# MCU_and_Power_Man.net
KiCad netlist of a schematic drawn in Altium Designer
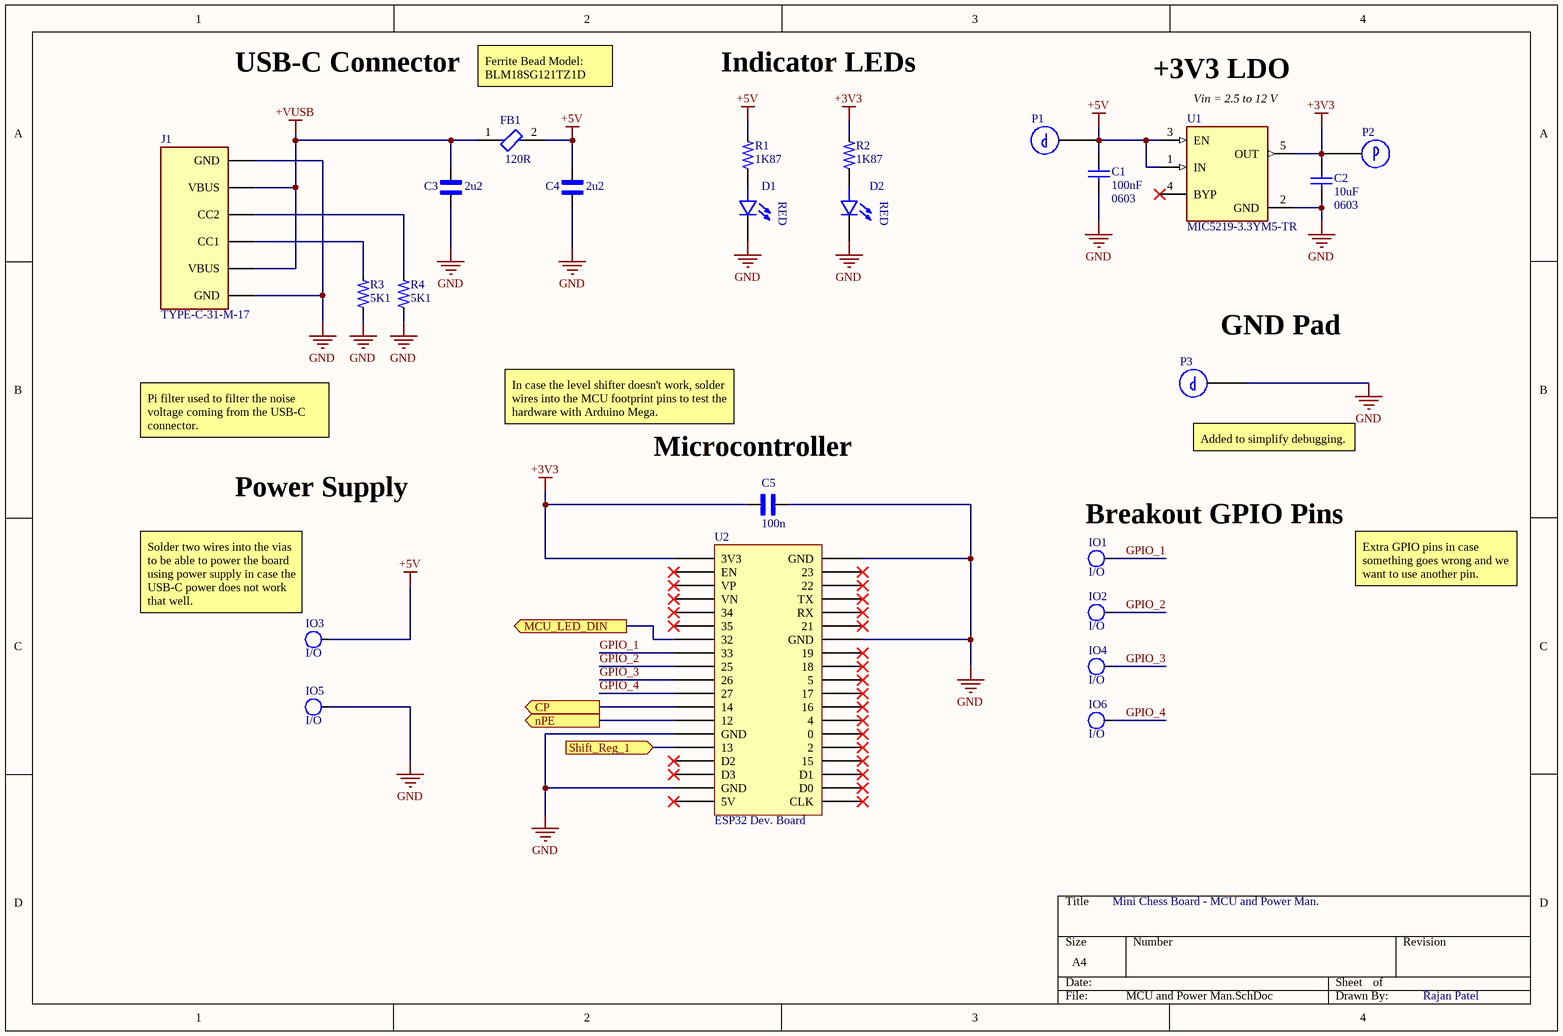
[diagram p0: MCU and Power Man.SchDoc]

(export (version "E")
  (design (tool "Eeschema 10.0.6"))
  (components
    (comp (ref "C1")
      (value "100nF")
      (footprint "CAP 0805")
      (description "Capacitor")
      (fields (field (name "ALTIUM_VALUE") "0603") (field (name "PUBLISHER") "Altium Limited"))
      (libsource (lib "Miscellaneous Devices") (part "Cap"))
    )
    (comp (ref "C2")
      (value "10uF")
      (footprint "CAP 0805")
      (description "Capacitor")
      (fields (field (name "ALTIUM_VALUE") "0603") (field (name "PUBLISHER") "Altium Limited"))
      (libsource (lib "Miscellaneous Devices") (part "Cap"))
    )
    (comp (ref "C3")
      (value "2u2")
      (footprint "CAP 0805")
      (libsource (lib "ChessBoardSchLib") (part "CAP 0805"))
    )
    (comp (ref "C4")
      (value "2u2")
      (footprint "CAP 0805")
      (libsource (lib "ChessBoardSchLib") (part "CAP 0805"))
    )
    (comp (ref "C5")
      (value "100n")
      (footprint "CAP 0805")
      (libsource (lib "ChessBoardSchLib") (part "CAP 0805"))
    )
    (comp (ref "D1")
      (value "LED 0805")
      (footprint "LED_0805")
      (description "Red LED Indication - Discrete 1.7V 0805 (2012 Metric)")
      (fields (field (name "MP") "7012X1"))
      (libsource (lib "ChessBoardSchLib") (part "LED 0805"))
    )
    (comp (ref "D2")
      (value "LED 0805")
      (footprint "LED_0805")
      (description "Red LED Indication - Discrete 1.7V 0805 (2012 Metric)")
      (fields (field (name "MP") "7012X1"))
      (libsource (lib "ChessBoardSchLib") (part "LED 0805"))
    )
    (comp (ref "FB1")
      (value "120R")
      (footprint "FP-BLM21-0_2-t0_85-e0_5-IPC_A")
      (description "FERRITE BEAD 120 OHM 0603 1LN")
      (fields (field (name "TOLERANCE") "25%"))
      (libsource (lib "Altium Content Vault") (part "5f30dd21d616792df468990f7003faa"))
    )
    (comp (ref "IO1") (value "I/O") (footprint "I/O") (libsource (lib "MiniChessBoardSchLib") (part "I/O")))
    (comp (ref "IO2") (value "I/O") (footprint "I/O") (libsource (lib "MiniChessBoardSchLib") (part "I/O")))
    (comp (ref "IO3") (value "I/O") (footprint "I/O") (libsource (lib "MiniChessBoardSchLib") (part "I/O")))
    (comp (ref "IO4") (value "I/O") (footprint "I/O") (libsource (lib "MiniChessBoardSchLib") (part "I/O")))
    (comp (ref "IO5") (value "I/O") (footprint "I/O") (libsource (lib "MiniChessBoardSchLib") (part "I/O")))
    (comp (ref "IO6") (value "I/O") (footprint "I/O") (libsource (lib "MiniChessBoardSchLib") (part "I/O")))
    (comp (ref "J1")
      (value "TYPE-C-31-M-17")
      (footprint "TYPEC31M17")
      (description "TYPE-C-31-M-17 HROPARTS")
      (fields (field (name "MF") "HRO Electronics Co., Ltd."))
      (libsource (lib "ChessBoardSchLib") (part "TYPE-C-31-M-17"))
    )
    (comp (ref "P1")
      (value "Probe_5019")
      (footprint "Testpoint")
      (description "Phosphor Bronze Contact Miniature Silver Plated Surface Mount Test Points")
      (fields
        (field (name "MANUFACTURER") "Keystone Electronics")
        (field (name "MANUFACTURER PART NUMBER") "5019")
      )
      (libsource (lib "MiniChessBoardSchLib") (part "Probe_5019"))
    )
    (comp (ref "P2")
      (value "Probe_5019")
      (footprint "Testpoint")
      (description "Phosphor Bronze Contact Miniature Silver Plated Surface Mount Test Points")
      (fields
        (field (name "MANUFACTURER") "Keystone Electronics")
        (field (name "MANUFACTURER PART NUMBER") "5019")
      )
      (libsource (lib "MiniChessBoardSchLib") (part "Probe_5019"))
    )
    (comp (ref "P3")
      (value "Probe_5019")
      (footprint "Testpoint")
      (description "Phosphor Bronze Contact Miniature Silver Plated Surface Mount Test Points")
      (fields
        (field (name "MANUFACTURER") "Keystone Electronics")
        (field (name "MANUFACTURER PART NUMBER") "5019")
      )
      (libsource (lib "MiniChessBoardSchLib") (part "Probe_5019"))
    )
    (comp (ref "R1")
      (value "1K87")
      (footprint "res 0805")
      (fields
        (field (name "MP") "2-2176053-2")
        (field (name "MF") "TE Connectivity")
        (field (name "TOLERANCE") "1%")
      )
      (libsource (lib "ChessBoardSchLib") (part "Resistor 0805"))
    )
    (comp (ref "R2")
      (value "1K87")
      (footprint "res 0805")
      (fields
        (field (name "MP") "2-2176053-2")
        (field (name "MF") "TE Connectivity")
        (field (name "TOLERANCE") "1%")
      )
      (libsource (lib "ChessBoardSchLib") (part "Resistor 0805"))
    )
    (comp (ref "R3")
      (value "5K1")
      (footprint "res 0805")
      (fields
        (field (name "MP") "2-2176053-2")
        (field (name "MF") "TE Connectivity")
        (field (name "TOLERANCE") "1%")
      )
      (libsource (lib "ChessBoardSchLib") (part "Resistor 0805"))
    )
    (comp (ref "R4")
      (value "5K1")
      (footprint "res 0805")
      (fields
        (field (name "MP") "2-2176053-2")
        (field (name "MF") "TE Connectivity")
        (field (name "TOLERANCE") "1%")
      )
      (libsource (lib "ChessBoardSchLib") (part "Resistor 0805"))
    )
    (comp (ref "U1")
      (value "MIC5219-3.3YM5-TR")
      (footprint "FP-SOT23-5LD-PL-1-IPC_C")
      (description "IC REG LINEAR 3.3V 500MA SOT23-5")
      (libsource (lib "Altium Content Vault") (part "16b36b16d6b7b40c29ab14718bc3058"))
    )
    (comp (ref "U2")
      (value "ESP32 Dev. Board")
      (footprint "ESPRESSIF_ESP32-DEVKITC-32UE")
      (fields
        (field (name "MANUFACTURER") "Espressif Systems")
        (field (name "MANUFACTURER PART NUMBER") "ESP32-DEVKITC-32UE")
      )
      (libsource (lib "ChessBoardSchLib") (part "ESP32 Dev. Board"))
    )
  )
  (nets
    (net (code "1") (name "+3V3") (class "Default")
      (node (ref "C2") (pin "2") (pinfunction "2_2") (pintype "passive"))
      (node (ref "C5") (pin "2") (pinfunction "2_2") (pintype "passive"))
      (node (ref "P2") (pin "1") (pinfunction "1_1") (pintype "passive"))
      (node (ref "R2") (pin "2") (pinfunction "2_2") (pintype "passive"))
      (node (ref "U1") (pin "5") (pinfunction "OUT_5") (pintype "output"))
      (node (ref "U2") (pin "1") (pinfunction "3V3_1") (pintype "passive"))
    )
    (net (code "2") (name "+5V") (class "Default")
      (node (ref "C1") (pin "2") (pinfunction "2_2") (pintype "passive"))
      (node (ref "C4") (pin "2") (pinfunction "2_2") (pintype "passive"))
      (node (ref "FB1") (pin "2") (pinfunction "2_2") (pintype "passive"))
      (node (ref "IO3") (pin "1") (pinfunction "1_1") (pintype "passive"))
      (node (ref "P1") (pin "1") (pinfunction "1_1") (pintype "passive"))
      (node (ref "R1") (pin "2") (pinfunction "2_2") (pintype "passive"))
      (node (ref "U1") (pin "1") (pinfunction "IN_1") (pintype "input"))
      (node (ref "U1") (pin "3") (pinfunction "EN_3") (pintype "input"))
    )
    (net (code "3") (name "+VUSB") (class "Default")
      (node (ref "C3") (pin "2") (pinfunction "2_2") (pintype "passive"))
      (node (ref "FB1") (pin "1") (pinfunction "1_1") (pintype "passive"))
      (node (ref "J1") (pin "2") (pinfunction "VBUS_2") (pintype "passive"))
      (node (ref "J1") (pin "5") (pinfunction "VBUS_5") (pintype "passive"))
    )
    (net (code "4") (name "/CP") (class "Default")
      (node (ref "U2") (pin "12") (pinfunction "14_12") (pintype "passive"))
    )
    (net (code "5") (name "/GPIO_1") (class "Default")
      (node (ref "IO1") (pin "1") (pinfunction "1_1") (pintype "passive"))
      (node (ref "U2") (pin "8") (pinfunction "33_8") (pintype "passive"))
    )
    (net (code "6") (name "/GPIO_2") (class "Default")
      (node (ref "IO2") (pin "1") (pinfunction "1_1") (pintype "passive"))
      (node (ref "U2") (pin "9") (pinfunction "25_9") (pintype "passive"))
    )
    (net (code "7") (name "/GPIO_3") (class "Default")
      (node (ref "IO4") (pin "1") (pinfunction "1_1") (pintype "passive"))
      (node (ref "U2") (pin "10") (pinfunction "26_10") (pintype "passive"))
    )
    (net (code "8") (name "/GPIO_4") (class "Default")
      (node (ref "IO6") (pin "1") (pinfunction "1_1") (pintype "passive"))
      (node (ref "U2") (pin "11") (pinfunction "27_11") (pintype "passive"))
    )
    (net (code "9") (name "/MCU_LED_DIN") (class "Default")
      (node (ref "U2") (pin "7") (pinfunction "32_7") (pintype "passive"))
    )
    (net (code "10") (name "/Shift_Reg_1") (class "Default")
      (node (ref "U2") (pin "15") (pinfunction "13_15") (pintype "passive"))
    )
    (net (code "11") (name "/nPE") (class "Default")
      (node (ref "U2") (pin "13") (pinfunction "12_13") (pintype "passive"))
    )
    (net (code "12") (name "GND") (class "Default")
      (node (ref "C1") (pin "1") (pinfunction "1_1") (pintype "passive"))
      (node (ref "C2") (pin "1") (pinfunction "1_1") (pintype "passive"))
      (node (ref "C3") (pin "1") (pinfunction "1_1") (pintype "passive"))
      (node (ref "C4") (pin "1") (pinfunction "1_1") (pintype "passive"))
      (node (ref "C5") (pin "1") (pinfunction "1_1") (pintype "passive"))
      (node (ref "D1") (pin "1") (pinfunction "C_1") (pintype "passive"))
      (node (ref "D2") (pin "1") (pinfunction "C_1") (pintype "passive"))
      (node (ref "IO5") (pin "1") (pinfunction "1_1") (pintype "passive"))
      (node (ref "J1") (pin "1") (pinfunction "GND_1") (pintype "passive"))
      (node (ref "J1") (pin "6") (pinfunction "GND_6") (pintype "passive"))
      (node (ref "P3") (pin "1") (pinfunction "1_1") (pintype "passive"))
      (node (ref "R3") (pin "1") (pinfunction "1_1") (pintype "passive"))
      (node (ref "R4") (pin "1") (pinfunction "1_1") (pintype "passive"))
      (node (ref "U1") (pin "2") (pinfunction "GND_2") (pintype "power_in"))
      (node (ref "U2") (pin "14") (pinfunction "GND_14") (pintype "passive"))
      (node (ref "U2") (pin "18") (pinfunction "GND_18") (pintype "passive"))
      (node (ref "U2") (pin "32") (pinfunction "GND_32") (pintype "passive"))
      (node (ref "U2") (pin "38") (pinfunction "GND_38") (pintype "passive"))
    )
    (net (code "13") (name "Net-(D1-A)") (class "Default")
      (node (ref "D1") (pin "2") (pinfunction "A_2") (pintype "passive"))
      (node (ref "R1") (pin "1") (pinfunction "1_1") (pintype "passive"))
    )
    (net (code "14") (name "Net-(D2-A)") (class "Default")
      (node (ref "D2") (pin "2") (pinfunction "A_2") (pintype "passive"))
      (node (ref "R2") (pin "1") (pinfunction "1_1") (pintype "passive"))
    )
    (net (code "15") (name "Net-(J1-CC1)") (class "Default")
      (node (ref "J1") (pin "3") (pinfunction "CC1_3") (pintype "passive"))
      (node (ref "R3") (pin "2") (pinfunction "2_2") (pintype "passive"))
    )
    (net (code "16") (name "Net-(J1-CC2)") (class "Default")
      (node (ref "J1") (pin "4") (pinfunction "CC2_4") (pintype "passive"))
      (node (ref "R4") (pin "2") (pinfunction "2_2") (pintype "passive"))
    )
    (net (code "17") (name "unconnected-(U1-BYP-Pad4)") (class "Default")
      (node (ref "U1") (pin "4") (pinfunction "BYP_4") (pintype "passive+no_connect"))
    )
    (net (code "18") (name "unconnected-(U2-0-Pad25)") (class "Default")
      (node (ref "U2") (pin "25") (pinfunction "0_25") (pintype "passive+no_connect"))
    )
    (net (code "19") (name "unconnected-(U2-2-Pad24)") (class "Default")
      (node (ref "U2") (pin "24") (pinfunction "2_24") (pintype "passive+no_connect"))
    )
    (net (code "20") (name "unconnected-(U2-4-Pad26)") (class "Default")
      (node (ref "U2") (pin "26") (pinfunction "4_26") (pintype "passive+no_connect"))
    )
    (net (code "21") (name "unconnected-(U2-5-Pad29)") (class "Default")
      (node (ref "U2") (pin "29") (pinfunction "5_29") (pintype "passive+no_connect"))
    )
    (net (code "22") (name "unconnected-(U2-5V-Pad19)") (class "Default")
      (node (ref "U2") (pin "19") (pinfunction "5V_19") (pintype "passive+no_connect"))
    )
    (net (code "23") (name "unconnected-(U2-15-Pad23)") (class "Default")
      (node (ref "U2") (pin "23") (pinfunction "15_23") (pintype "passive+no_connect"))
    )
    (net (code "24") (name "unconnected-(U2-16-Pad27)") (class "Default")
      (node (ref "U2") (pin "27") (pinfunction "16_27") (pintype "passive+no_connect"))
    )
    (net (code "25") (name "unconnected-(U2-17-Pad28)") (class "Default")
      (node (ref "U2") (pin "28") (pinfunction "17_28") (pintype "passive+no_connect"))
    )
    (net (code "26") (name "unconnected-(U2-18-Pad30)") (class "Default")
      (node (ref "U2") (pin "30") (pinfunction "18_30") (pintype "passive+no_connect"))
    )
    (net (code "27") (name "unconnected-(U2-19-Pad31)") (class "Default")
      (node (ref "U2") (pin "31") (pinfunction "19_31") (pintype "passive+no_connect"))
    )
    (net (code "28") (name "unconnected-(U2-21-Pad33)") (class "Default")
      (node (ref "U2") (pin "33") (pinfunction "21_33") (pintype "passive+no_connect"))
    )
    (net (code "29") (name "unconnected-(U2-22-Pad36)") (class "Default")
      (node (ref "U2") (pin "36") (pinfunction "22_36") (pintype "passive+no_connect"))
    )
    (net (code "30") (name "unconnected-(U2-23-Pad37)") (class "Default")
      (node (ref "U2") (pin "37") (pinfunction "23_37") (pintype "passive+no_connect"))
    )
    (net (code "31") (name "unconnected-(U2-34-Pad5)") (class "Default")
      (node (ref "U2") (pin "5") (pinfunction "34_5") (pintype "passive+no_connect"))
    )
    (net (code "32") (name "unconnected-(U2-35-Pad6)") (class "Default")
      (node (ref "U2") (pin "6") (pinfunction "35_6") (pintype "passive+no_connect"))
    )
    (net (code "33") (name "unconnected-(U2-CLK-Pad20)") (class "Default")
      (node (ref "U2") (pin "20") (pinfunction "CLK_20") (pintype "passive+no_connect"))
    )
    (net (code "34") (name "unconnected-(U2-D0-Pad21)") (class "Default")
      (node (ref "U2") (pin "21") (pinfunction "D0_21") (pintype "passive+no_connect"))
    )
    (net (code "35") (name "unconnected-(U2-D1-Pad22)") (class "Default")
      (node (ref "U2") (pin "22") (pinfunction "D1_22") (pintype "passive+no_connect"))
    )
    (net (code "36") (name "unconnected-(U2-D2-Pad16)") (class "Default")
      (node (ref "U2") (pin "16") (pinfunction "D2_16") (pintype "passive+no_connect"))
    )
    (net (code "37") (name "unconnected-(U2-D3-Pad17)") (class "Default")
      (node (ref "U2") (pin "17") (pinfunction "D3_17") (pintype "passive+no_connect"))
    )
    (net (code "38") (name "unconnected-(U2-EN-Pad2)") (class "Default")
      (node (ref "U2") (pin "2") (pinfunction "EN_2") (pintype "passive+no_connect"))
    )
    (net (code "39") (name "unconnected-(U2-RX-Pad34)") (class "Default")
      (node (ref "U2") (pin "34") (pinfunction "RX_34") (pintype "passive+no_connect"))
    )
    (net (code "40") (name "unconnected-(U2-TX-Pad35)") (class "Default")
      (node (ref "U2") (pin "35") (pinfunction "TX_35") (pintype "passive+no_connect"))
    )
    (net (code "41") (name "unconnected-(U2-VN-Pad4)") (class "Default")
      (node (ref "U2") (pin "4") (pinfunction "VN_4") (pintype "passive+no_connect"))
    )
    (net (code "42") (name "unconnected-(U2-VP-Pad3)") (class "Default")
      (node (ref "U2") (pin "3") (pinfunction "VP_3") (pintype "passive+no_connect"))
    )
  )
)
